# AutoCar_1.net
KiCad netlist of a schematic drawn in EAGLE
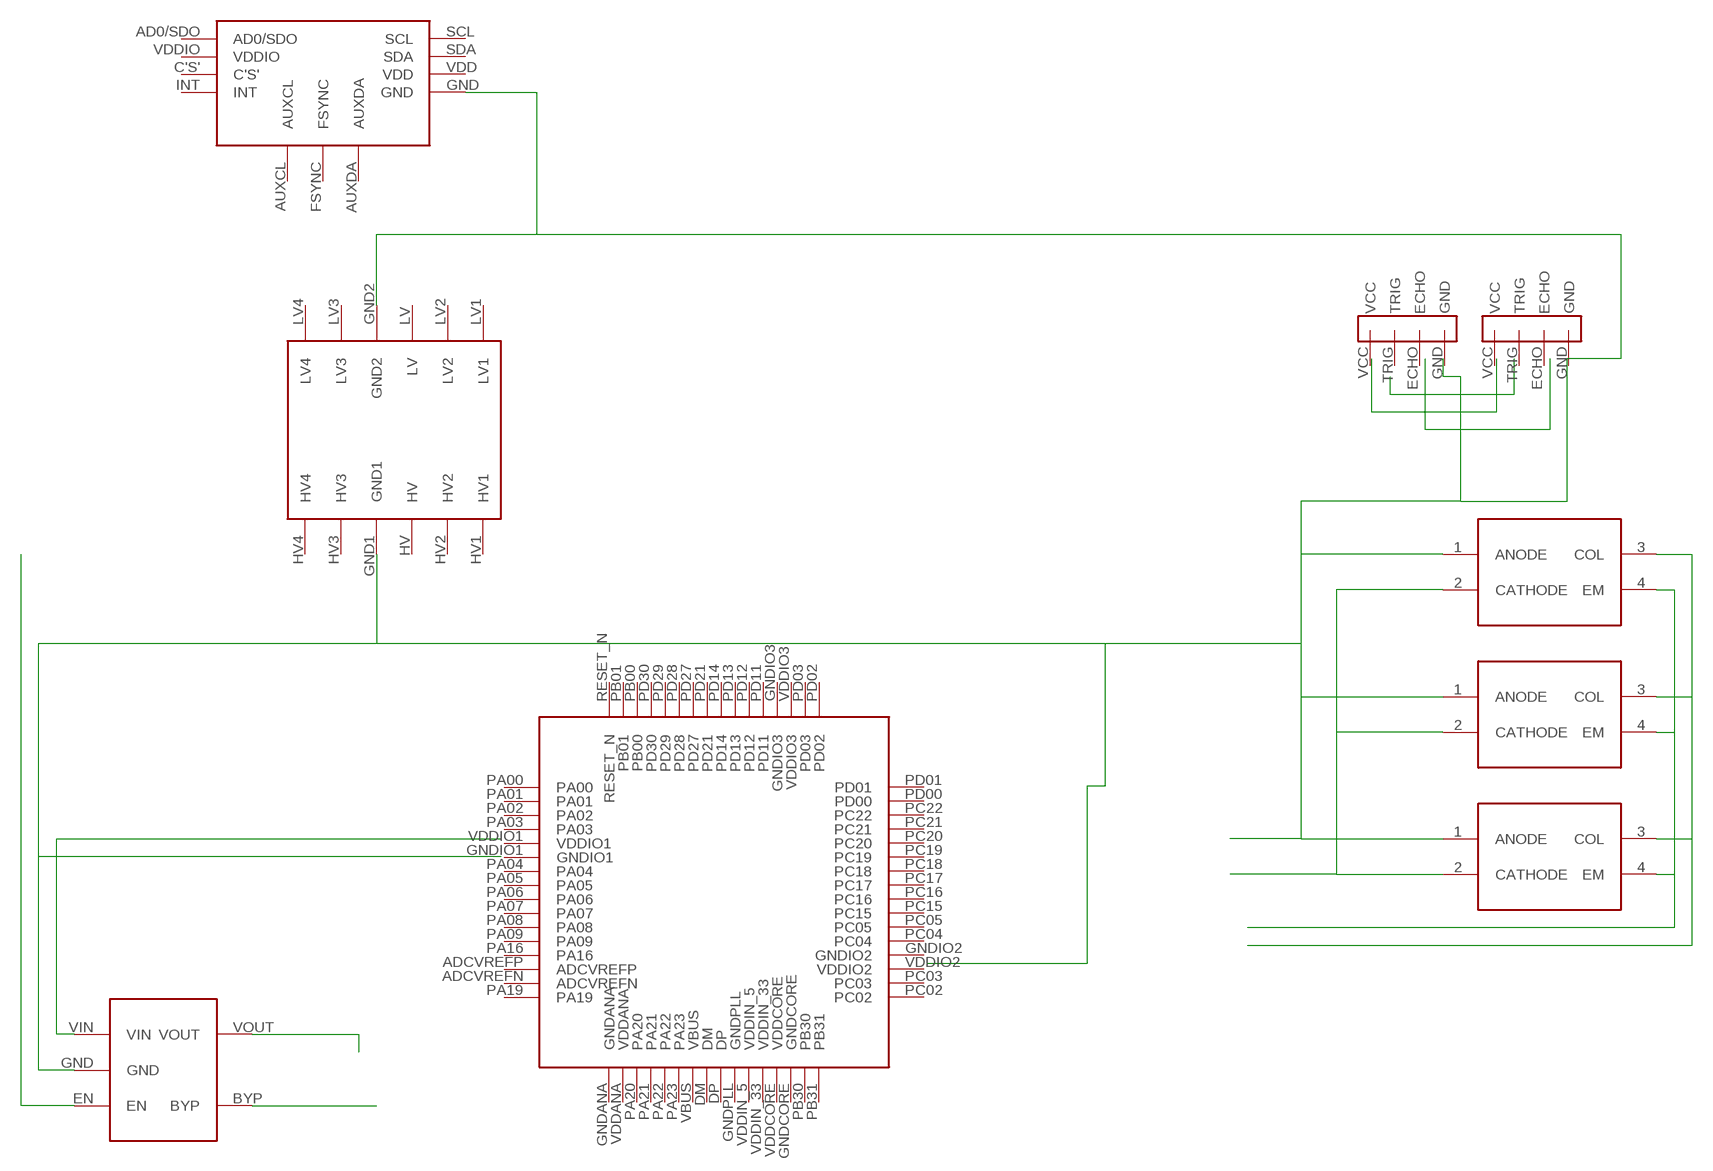
[diagram p0: schematic, sheet 1]

(export (version "E")
  (design (tool "Eeschema 10.0.6"))
  (components
    (comp (ref "U$1")
      (value "AT32UC3C2512C-A2UT")
      (footprint "eagle-import:TQFP-64")
      (libsource (lib "eagle-import") (part "AT32UC3C2512C-A2UT"))
    )
    (comp (ref "U$2")
      (value "QRE1113GR")
      (footprint "eagle-import:4-SMD")
      (libsource (lib "eagle-import") (part "QRE1113GR"))
    )
    (comp (ref "U$3")
      (value "QRE1113GR")
      (footprint "eagle-import:4-SMD")
      (libsource (lib "eagle-import") (part "QRE1113GR"))
    )
    (comp (ref "U$4")
      (value "QRE1113GR")
      (footprint "eagle-import:4-SMD")
      (libsource (lib "eagle-import") (part "QRE1113GR"))
    )
    (comp (ref "U$5")
      (value "SEN-15569")
      (footprint "eagle-import:HC-SR04")
      (libsource (lib "eagle-import") (part "SEN-15569"))
    )
    (comp (ref "U$6")
      (value "SEN-15569")
      (footprint "eagle-import:HC-SR04")
      (libsource (lib "eagle-import") (part "SEN-15569"))
    )
    (comp (ref "U$7")
      (value "AP2210K-5.0TRG1")
      (footprint "eagle-import:SC-74A")
      (libsource (lib "eagle-import") (part "AP2210K-5.0TRG1"))
    )
    (comp (ref "U$8")
      (value "SEN-13762")
      (footprint "eagle-import:MPU-9250")
      (libsource (lib "eagle-import") (part "SEN-13762"))
    )
    (comp (ref "U$9")
      (value "BOB-12009")
      (footprint "eagle-import:BSS138")
      (libsource (lib "eagle-import") (part "BOB-12009"))
    )
  )
  (nets
    (net (code "1") (name "Net-(U$2-ANODE)") (class "Default")
      (node (ref "U$2") (pin "1") (pinfunction "ANODE_1") (pintype "bidirectional"))
      (node (ref "U$3") (pin "1") (pinfunction "ANODE_1") (pintype "bidirectional"))
      (node (ref "U$4") (pin "1") (pinfunction "ANODE_1") (pintype "bidirectional"))
      (node (ref "U$7") (pin "GND") (pinfunction "GND_GND") (pintype "bidirectional"))
      (node (ref "U$8") (pin "GND") (pinfunction "GND_GND") (pintype "bidirectional"))
      (node (ref "U$9") (pin "GND1") (pinfunction "GND1_GND1") (pintype "bidirectional"))
      (node (ref "U$9") (pin "GND2") (pinfunction "GND2_GND2") (pintype "bidirectional"))
    )
    (net (code "2") (name "Net-(U$2-CATHODE)") (class "Default")
      (node (ref "U$2") (pin "2") (pinfunction "CATHODE_2") (pintype "bidirectional"))
      (node (ref "U$3") (pin "2") (pinfunction "CATHODE_2") (pintype "bidirectional"))
      (node (ref "U$4") (pin "2") (pinfunction "CATHODE_2") (pintype "bidirectional"))
    )
    (net (code "3") (name "Net-(U$2-COL)") (class "Default")
      (node (ref "U$2") (pin "3") (pinfunction "COL_3") (pintype "bidirectional"))
      (node (ref "U$3") (pin "3") (pinfunction "COL_3") (pintype "bidirectional"))
      (node (ref "U$4") (pin "3") (pinfunction "COL_3") (pintype "bidirectional"))
    )
    (net (code "4") (name "Net-(U$2-EM)") (class "Default")
      (node (ref "U$2") (pin "4") (pinfunction "EM_4") (pintype "bidirectional"))
      (node (ref "U$3") (pin "4") (pinfunction "EM_4") (pintype "bidirectional"))
      (node (ref "U$4") (pin "4") (pinfunction "EM_4") (pintype "bidirectional"))
    )
    (net (code "5") (name "unconnected-(U$1-PadADCVREFN)") (class "Default")
      (node (ref "U$1") (pin "ADCVREFN") (pinfunction "ADCVREFN_ADCVREFN") (pintype "bidirectional"))
    )
    (net (code "6") (name "unconnected-(U$1-PadADCVREFP)") (class "Default")
      (node (ref "U$1") (pin "ADCVREFP") (pinfunction "ADCVREFP_ADCVREFP") (pintype "bidirectional"))
    )
    (net (code "7") (name "unconnected-(U$1-PadDM)") (class "Default")
      (node (ref "U$1") (pin "DM") (pinfunction "DM_DM") (pintype "bidirectional"))
    )
    (net (code "8") (name "unconnected-(U$1-PadDP)") (class "Default")
      (node (ref "U$1") (pin "DP") (pinfunction "DP_DP") (pintype "bidirectional"))
    )
    (net (code "9") (name "unconnected-(U$1-PadGNDANA)") (class "Default")
      (node (ref "U$1") (pin "GNDANA") (pinfunction "GNDANA_GNDANA") (pintype "bidirectional"))
    )
    (net (code "10") (name "unconnected-(U$1-PadGNDCORE)") (class "Default")
      (node (ref "U$1") (pin "GNDCORE") (pinfunction "GNDCORE_GNDCORE") (pintype "bidirectional"))
    )
    (net (code "11") (name "unconnected-(U$1-PadGNDIO1)") (class "Default")
      (node (ref "U$1") (pin "GNDIO1") (pinfunction "GNDIO1_GNDIO1") (pintype "bidirectional"))
    )
    (net (code "12") (name "unconnected-(U$1-PadGNDIO2)") (class "Default")
      (node (ref "U$1") (pin "GNDIO2") (pinfunction "GNDIO2_GNDIO2") (pintype "bidirectional"))
    )
    (net (code "13") (name "unconnected-(U$1-PadGNDIO3)") (class "Default")
      (node (ref "U$1") (pin "GNDIO3") (pinfunction "GNDIO3_GNDIO3") (pintype "bidirectional"))
    )
    (net (code "14") (name "unconnected-(U$1-PadGNDPLL)") (class "Default")
      (node (ref "U$1") (pin "GNDPLL") (pinfunction "GNDPLL_GNDPLL") (pintype "bidirectional"))
    )
    (net (code "15") (name "unconnected-(U$1-PadPA00)") (class "Default")
      (node (ref "U$1") (pin "PA00") (pinfunction "PA00_PA00") (pintype "bidirectional"))
    )
    (net (code "16") (name "unconnected-(U$1-PadPA01)") (class "Default")
      (node (ref "U$1") (pin "PA01") (pinfunction "PA01_PA01") (pintype "bidirectional"))
    )
    (net (code "17") (name "unconnected-(U$1-PadPA02)") (class "Default")
      (node (ref "U$1") (pin "PA02") (pinfunction "PA02_PA02") (pintype "bidirectional"))
    )
    (net (code "18") (name "unconnected-(U$1-PadPA03)") (class "Default")
      (node (ref "U$1") (pin "PA03") (pinfunction "PA03_PA03") (pintype "bidirectional"))
    )
    (net (code "19") (name "unconnected-(U$1-PadPA04)") (class "Default")
      (node (ref "U$1") (pin "PA04") (pinfunction "PA04_PA04") (pintype "bidirectional"))
    )
    (net (code "20") (name "unconnected-(U$1-PadPA05)") (class "Default")
      (node (ref "U$1") (pin "PA05") (pinfunction "PA05_PA05") (pintype "bidirectional"))
    )
    (net (code "21") (name "unconnected-(U$1-PadPA06)") (class "Default")
      (node (ref "U$1") (pin "PA06") (pinfunction "PA06_PA06") (pintype "bidirectional"))
    )
    (net (code "22") (name "unconnected-(U$1-PadPA07)") (class "Default")
      (node (ref "U$1") (pin "PA07") (pinfunction "PA07_PA07") (pintype "bidirectional"))
    )
    (net (code "23") (name "unconnected-(U$1-PadPA08)") (class "Default")
      (node (ref "U$1") (pin "PA08") (pinfunction "PA08_PA08") (pintype "bidirectional"))
    )
    (net (code "24") (name "unconnected-(U$1-PadPA09)") (class "Default")
      (node (ref "U$1") (pin "PA09") (pinfunction "PA09_PA09") (pintype "bidirectional"))
    )
    (net (code "25") (name "unconnected-(U$1-PadPA16)") (class "Default")
      (node (ref "U$1") (pin "PA16") (pinfunction "PA16_PA16") (pintype "bidirectional"))
    )
    (net (code "26") (name "unconnected-(U$1-PadPA19)") (class "Default")
      (node (ref "U$1") (pin "PA19") (pinfunction "PA19_PA19") (pintype "bidirectional"))
    )
    (net (code "27") (name "unconnected-(U$1-PadPA20)") (class "Default")
      (node (ref "U$1") (pin "PA20") (pinfunction "PA20_PA20") (pintype "bidirectional"))
    )
    (net (code "28") (name "unconnected-(U$1-PadPA21)") (class "Default")
      (node (ref "U$1") (pin "PA21") (pinfunction "PA21_PA21") (pintype "bidirectional"))
    )
    (net (code "29") (name "unconnected-(U$1-PadPA22)") (class "Default")
      (node (ref "U$1") (pin "PA22") (pinfunction "PA22_PA22") (pintype "bidirectional"))
    )
    (net (code "30") (name "unconnected-(U$1-PadPA23)") (class "Default")
      (node (ref "U$1") (pin "PA23") (pinfunction "PA23_PA23") (pintype "bidirectional"))
    )
    (net (code "31") (name "unconnected-(U$1-PadPB00)") (class "Default")
      (node (ref "U$1") (pin "PB00") (pinfunction "PB00_PB00") (pintype "bidirectional"))
    )
    (net (code "32") (name "unconnected-(U$1-PadPB01)") (class "Default")
      (node (ref "U$1") (pin "PB01") (pinfunction "PB01_PB01") (pintype "bidirectional"))
    )
    (net (code "33") (name "unconnected-(U$1-PadPB30)") (class "Default")
      (node (ref "U$1") (pin "PB30") (pinfunction "PB30_PB30") (pintype "bidirectional"))
    )
    (net (code "34") (name "unconnected-(U$1-PadPB31)") (class "Default")
      (node (ref "U$1") (pin "PB31") (pinfunction "PB31_PB31") (pintype "bidirectional"))
    )
    (net (code "35") (name "unconnected-(U$1-PadPC02)") (class "Default")
      (node (ref "U$1") (pin "PC02") (pinfunction "PC02_PC02") (pintype "bidirectional"))
    )
    (net (code "36") (name "unconnected-(U$1-PadPC03)") (class "Default")
      (node (ref "U$1") (pin "PC03") (pinfunction "PC03_PC03") (pintype "bidirectional"))
    )
    (net (code "37") (name "unconnected-(U$1-PadPC04)") (class "Default")
      (node (ref "U$1") (pin "PC04") (pinfunction "PC04_PC04") (pintype "bidirectional"))
    )
    (net (code "38") (name "unconnected-(U$1-PadPC05)") (class "Default")
      (node (ref "U$1") (pin "PC05") (pinfunction "PC05_PC05") (pintype "bidirectional"))
    )
    (net (code "39") (name "unconnected-(U$1-PadPC15)") (class "Default")
      (node (ref "U$1") (pin "PC15") (pinfunction "PC15_PC15") (pintype "bidirectional"))
    )
    (net (code "40") (name "unconnected-(U$1-PadPC16)") (class "Default")
      (node (ref "U$1") (pin "PC16") (pinfunction "PC16_PC16") (pintype "bidirectional"))
    )
    (net (code "41") (name "unconnected-(U$1-PadPC17)") (class "Default")
      (node (ref "U$1") (pin "PC17") (pinfunction "PC17_PC17") (pintype "bidirectional"))
    )
    (net (code "42") (name "unconnected-(U$1-PadPC18)") (class "Default")
      (node (ref "U$1") (pin "PC18") (pinfunction "PC18_PC18") (pintype "bidirectional"))
    )
    (net (code "43") (name "unconnected-(U$1-PadPC19)") (class "Default")
      (node (ref "U$1") (pin "PC19") (pinfunction "PC19_PC19") (pintype "bidirectional"))
    )
    (net (code "44") (name "unconnected-(U$1-PadPC20)") (class "Default")
      (node (ref "U$1") (pin "PC20") (pinfunction "PC20_PC20") (pintype "bidirectional"))
    )
    (net (code "45") (name "unconnected-(U$1-PadPC21)") (class "Default")
      (node (ref "U$1") (pin "PC21") (pinfunction "PC21_PC21") (pintype "bidirectional"))
    )
    (net (code "46") (name "unconnected-(U$1-PadPC22)") (class "Default")
      (node (ref "U$1") (pin "PC22") (pinfunction "PC22_PC22") (pintype "bidirectional"))
    )
    (net (code "47") (name "unconnected-(U$1-PadPD00)") (class "Default")
      (node (ref "U$1") (pin "PD00") (pinfunction "PD00_PD00") (pintype "bidirectional"))
    )
    (net (code "48") (name "unconnected-(U$1-PadPD01)") (class "Default")
      (node (ref "U$1") (pin "PD01") (pinfunction "PD01_PD01") (pintype "bidirectional"))
    )
    (net (code "49") (name "unconnected-(U$1-PadPD02)") (class "Default")
      (node (ref "U$1") (pin "PD02") (pinfunction "PD02_PD02") (pintype "bidirectional"))
    )
    (net (code "50") (name "unconnected-(U$1-PadPD03)") (class "Default")
      (node (ref "U$1") (pin "PD03") (pinfunction "PD03_PD03") (pintype "bidirectional"))
    )
    (net (code "51") (name "unconnected-(U$1-PadPD11)") (class "Default")
      (node (ref "U$1") (pin "PD11") (pinfunction "PD11_PD11") (pintype "bidirectional"))
    )
    (net (code "52") (name "unconnected-(U$1-PadPD12)") (class "Default")
      (node (ref "U$1") (pin "PD12") (pinfunction "PD12_PD12") (pintype "bidirectional"))
    )
    (net (code "53") (name "unconnected-(U$1-PadPD13)") (class "Default")
      (node (ref "U$1") (pin "PD13") (pinfunction "PD13_PD13") (pintype "bidirectional"))
    )
    (net (code "54") (name "unconnected-(U$1-PadPD14)") (class "Default")
      (node (ref "U$1") (pin "PD14") (pinfunction "PD14_PD14") (pintype "bidirectional"))
    )
    (net (code "55") (name "unconnected-(U$1-PadPD21)") (class "Default")
      (node (ref "U$1") (pin "PD21") (pinfunction "PD21_PD21") (pintype "bidirectional"))
    )
    (net (code "56") (name "unconnected-(U$1-PadPD27)") (class "Default")
      (node (ref "U$1") (pin "PD27") (pinfunction "PD27_PD27") (pintype "bidirectional"))
    )
    (net (code "57") (name "unconnected-(U$1-PadPD28)") (class "Default")
      (node (ref "U$1") (pin "PD28") (pinfunction "PD28_PD28") (pintype "bidirectional"))
    )
    (net (code "58") (name "unconnected-(U$1-PadPD29)") (class "Default")
      (node (ref "U$1") (pin "PD29") (pinfunction "PD29_PD29") (pintype "bidirectional"))
    )
    (net (code "59") (name "unconnected-(U$1-PadPD30)") (class "Default")
      (node (ref "U$1") (pin "PD30") (pinfunction "PD30_PD30") (pintype "bidirectional"))
    )
    (net (code "60") (name "unconnected-(U$1-PadRESET_N)") (class "Default")
      (node (ref "U$1") (pin "RESET_N") (pinfunction "RESET_N_RESET_N") (pintype "bidirectional"))
    )
    (net (code "61") (name "unconnected-(U$1-PadVBUS)") (class "Default")
      (node (ref "U$1") (pin "VBUS") (pinfunction "VBUS_VBUS") (pintype "bidirectional"))
    )
    (net (code "62") (name "unconnected-(U$1-PadVDDANA)") (class "Default")
      (node (ref "U$1") (pin "VDDANA") (pinfunction "VDDANA_VDDANA") (pintype "bidirectional"))
    )
    (net (code "63") (name "unconnected-(U$1-PadVDDCORE)") (class "Default")
      (node (ref "U$1") (pin "VDDCORE") (pinfunction "VDDCORE_VDDCORE") (pintype "bidirectional"))
    )
    (net (code "64") (name "unconnected-(U$1-PadVDDIN_5)") (class "Default")
      (node (ref "U$1") (pin "VDDIN_5") (pinfunction "VDDIN_5_VDDIN_5") (pintype "bidirectional"))
    )
    (net (code "65") (name "unconnected-(U$1-PadVDDIN_33)") (class "Default")
      (node (ref "U$1") (pin "VDDIN_33") (pinfunction "VDDIN_33_VDDIN_33") (pintype "bidirectional"))
    )
    (net (code "66") (name "unconnected-(U$1-PadVDDIO1)") (class "Default")
      (node (ref "U$1") (pin "VDDIO1") (pinfunction "VDDIO1_VDDIO1") (pintype "bidirectional"))
    )
    (net (code "67") (name "unconnected-(U$1-PadVDDIO2)") (class "Default")
      (node (ref "U$1") (pin "VDDIO2") (pinfunction "VDDIO2_VDDIO2") (pintype "bidirectional"))
    )
    (net (code "68") (name "unconnected-(U$1-PadVDDIO3)") (class "Default")
      (node (ref "U$1") (pin "VDDIO3") (pinfunction "VDDIO3_VDDIO3") (pintype "bidirectional"))
    )
    (net (code "69") (name "unconnected-(U$5-PadECHO)") (class "Default")
      (node (ref "U$5") (pin "ECHO") (pinfunction "ECHO_ECHO") (pintype "bidirectional"))
    )
    (net (code "70") (name "unconnected-(U$5-PadGND)") (class "Default")
      (node (ref "U$5") (pin "GND") (pinfunction "GND_GND") (pintype "bidirectional"))
    )
    (net (code "71") (name "unconnected-(U$5-PadTRIG)") (class "Default")
      (node (ref "U$5") (pin "TRIG") (pinfunction "TRIG_TRIG") (pintype "bidirectional"))
    )
    (net (code "72") (name "unconnected-(U$5-PadVCC)") (class "Default")
      (node (ref "U$5") (pin "VCC") (pinfunction "VCC_VCC") (pintype "bidirectional"))
    )
    (net (code "73") (name "unconnected-(U$6-PadECHO)") (class "Default")
      (node (ref "U$6") (pin "ECHO") (pinfunction "ECHO_ECHO") (pintype "bidirectional"))
    )
    (net (code "74") (name "unconnected-(U$6-PadGND)") (class "Default")
      (node (ref "U$6") (pin "GND") (pinfunction "GND_GND") (pintype "bidirectional"))
    )
    (net (code "75") (name "unconnected-(U$6-PadTRIG)") (class "Default")
      (node (ref "U$6") (pin "TRIG") (pinfunction "TRIG_TRIG") (pintype "bidirectional"))
    )
    (net (code "76") (name "unconnected-(U$6-PadVCC)") (class "Default")
      (node (ref "U$6") (pin "VCC") (pinfunction "VCC_VCC") (pintype "bidirectional"))
    )
    (net (code "77") (name "unconnected-(U$7-PadBYP)") (class "Default")
      (node (ref "U$7") (pin "BYP") (pinfunction "BYP_BYP") (pintype "bidirectional"))
    )
    (net (code "78") (name "unconnected-(U$7-PadEN)") (class "Default")
      (node (ref "U$7") (pin "EN") (pinfunction "EN_EN") (pintype "bidirectional"))
    )
    (net (code "79") (name "unconnected-(U$7-PadVIN)") (class "Default")
      (node (ref "U$7") (pin "VIN") (pinfunction "VIN_VIN") (pintype "bidirectional"))
    )
    (net (code "80") (name "unconnected-(U$7-PadVOUT)") (class "Default")
      (node (ref "U$7") (pin "VOUT") (pinfunction "VOUT_VOUT") (pintype "bidirectional"))
    )
    (net (code "81") (name "unconnected-(U$8-PadAD0{slash}SDO)") (class "Default")
      (node (ref "U$8") (pin "AD0/SDO") (pinfunction "AD0/SDO_AD0/SDO") (pintype "bidirectional"))
    )
    (net (code "82") (name "unconnected-(U$8-PadAUXCL)") (class "Default")
      (node (ref "U$8") (pin "AUXCL") (pinfunction "AUXCL_AUXCL") (pintype "bidirectional"))
    )
    (net (code "83") (name "unconnected-(U$8-PadAUXDA)") (class "Default")
      (node (ref "U$8") (pin "AUXDA") (pinfunction "AUXDA_AUXDA") (pintype "bidirectional"))
    )
    (net (code "84") (name "unconnected-(U$8-PadC'S')") (class "Default")
      (node (ref "U$8") (pin "C'S'") (pinfunction "C'S'_C'S'") (pintype "bidirectional"))
    )
    (net (code "85") (name "unconnected-(U$8-PadFSYNC)") (class "Default")
      (node (ref "U$8") (pin "FSYNC") (pinfunction "FSYNC_FSYNC") (pintype "bidirectional"))
    )
    (net (code "86") (name "unconnected-(U$8-PadINT)") (class "Default")
      (node (ref "U$8") (pin "INT") (pinfunction "INT_INT") (pintype "bidirectional"))
    )
    (net (code "87") (name "unconnected-(U$8-PadSCL)") (class "Default")
      (node (ref "U$8") (pin "SCL") (pinfunction "SCL_SCL") (pintype "bidirectional"))
    )
    (net (code "88") (name "unconnected-(U$8-PadSDA)") (class "Default")
      (node (ref "U$8") (pin "SDA") (pinfunction "SDA_SDA") (pintype "bidirectional"))
    )
    (net (code "89") (name "unconnected-(U$8-PadVDD)") (class "Default")
      (node (ref "U$8") (pin "VDD") (pinfunction "VDD_VDD") (pintype "bidirectional"))
    )
    (net (code "90") (name "unconnected-(U$8-PadVDDIO)") (class "Default")
      (node (ref "U$8") (pin "VDDIO") (pinfunction "VDDIO_VDDIO") (pintype "bidirectional"))
    )
    (net (code "91") (name "unconnected-(U$9-PadHV)") (class "Default")
      (node (ref "U$9") (pin "HV") (pinfunction "HV_HV") (pintype "bidirectional"))
    )
    (net (code "92") (name "unconnected-(U$9-PadHV1)") (class "Default")
      (node (ref "U$9") (pin "HV1") (pinfunction "HV1_HV1") (pintype "bidirectional"))
    )
    (net (code "93") (name "unconnected-(U$9-PadHV2)") (class "Default")
      (node (ref "U$9") (pin "HV2") (pinfunction "HV2_HV2") (pintype "bidirectional"))
    )
    (net (code "94") (name "unconnected-(U$9-PadHV3)") (class "Default")
      (node (ref "U$9") (pin "HV3") (pinfunction "HV3_HV3") (pintype "bidirectional"))
    )
    (net (code "95") (name "unconnected-(U$9-PadHV4)") (class "Default")
      (node (ref "U$9") (pin "HV4") (pinfunction "HV4_HV4") (pintype "bidirectional"))
    )
    (net (code "96") (name "unconnected-(U$9-PadLV)") (class "Default")
      (node (ref "U$9") (pin "LV") (pinfunction "LV_LV") (pintype "bidirectional"))
    )
    (net (code "97") (name "unconnected-(U$9-PadLV1)") (class "Default")
      (node (ref "U$9") (pin "LV1") (pinfunction "LV1_LV1") (pintype "bidirectional"))
    )
    (net (code "98") (name "unconnected-(U$9-PadLV2)") (class "Default")
      (node (ref "U$9") (pin "LV2") (pinfunction "LV2_LV2") (pintype "bidirectional"))
    )
    (net (code "99") (name "unconnected-(U$9-PadLV3)") (class "Default")
      (node (ref "U$9") (pin "LV3") (pinfunction "LV3_LV3") (pintype "bidirectional"))
    )
    (net (code "100") (name "unconnected-(U$9-PadLV4)") (class "Default")
      (node (ref "U$9") (pin "LV4") (pinfunction "LV4_LV4") (pintype "bidirectional"))
    )
  )
)
